# SparkFun_Si4707_Breakout.net
KiCad netlist of a schematic drawn in EAGLE
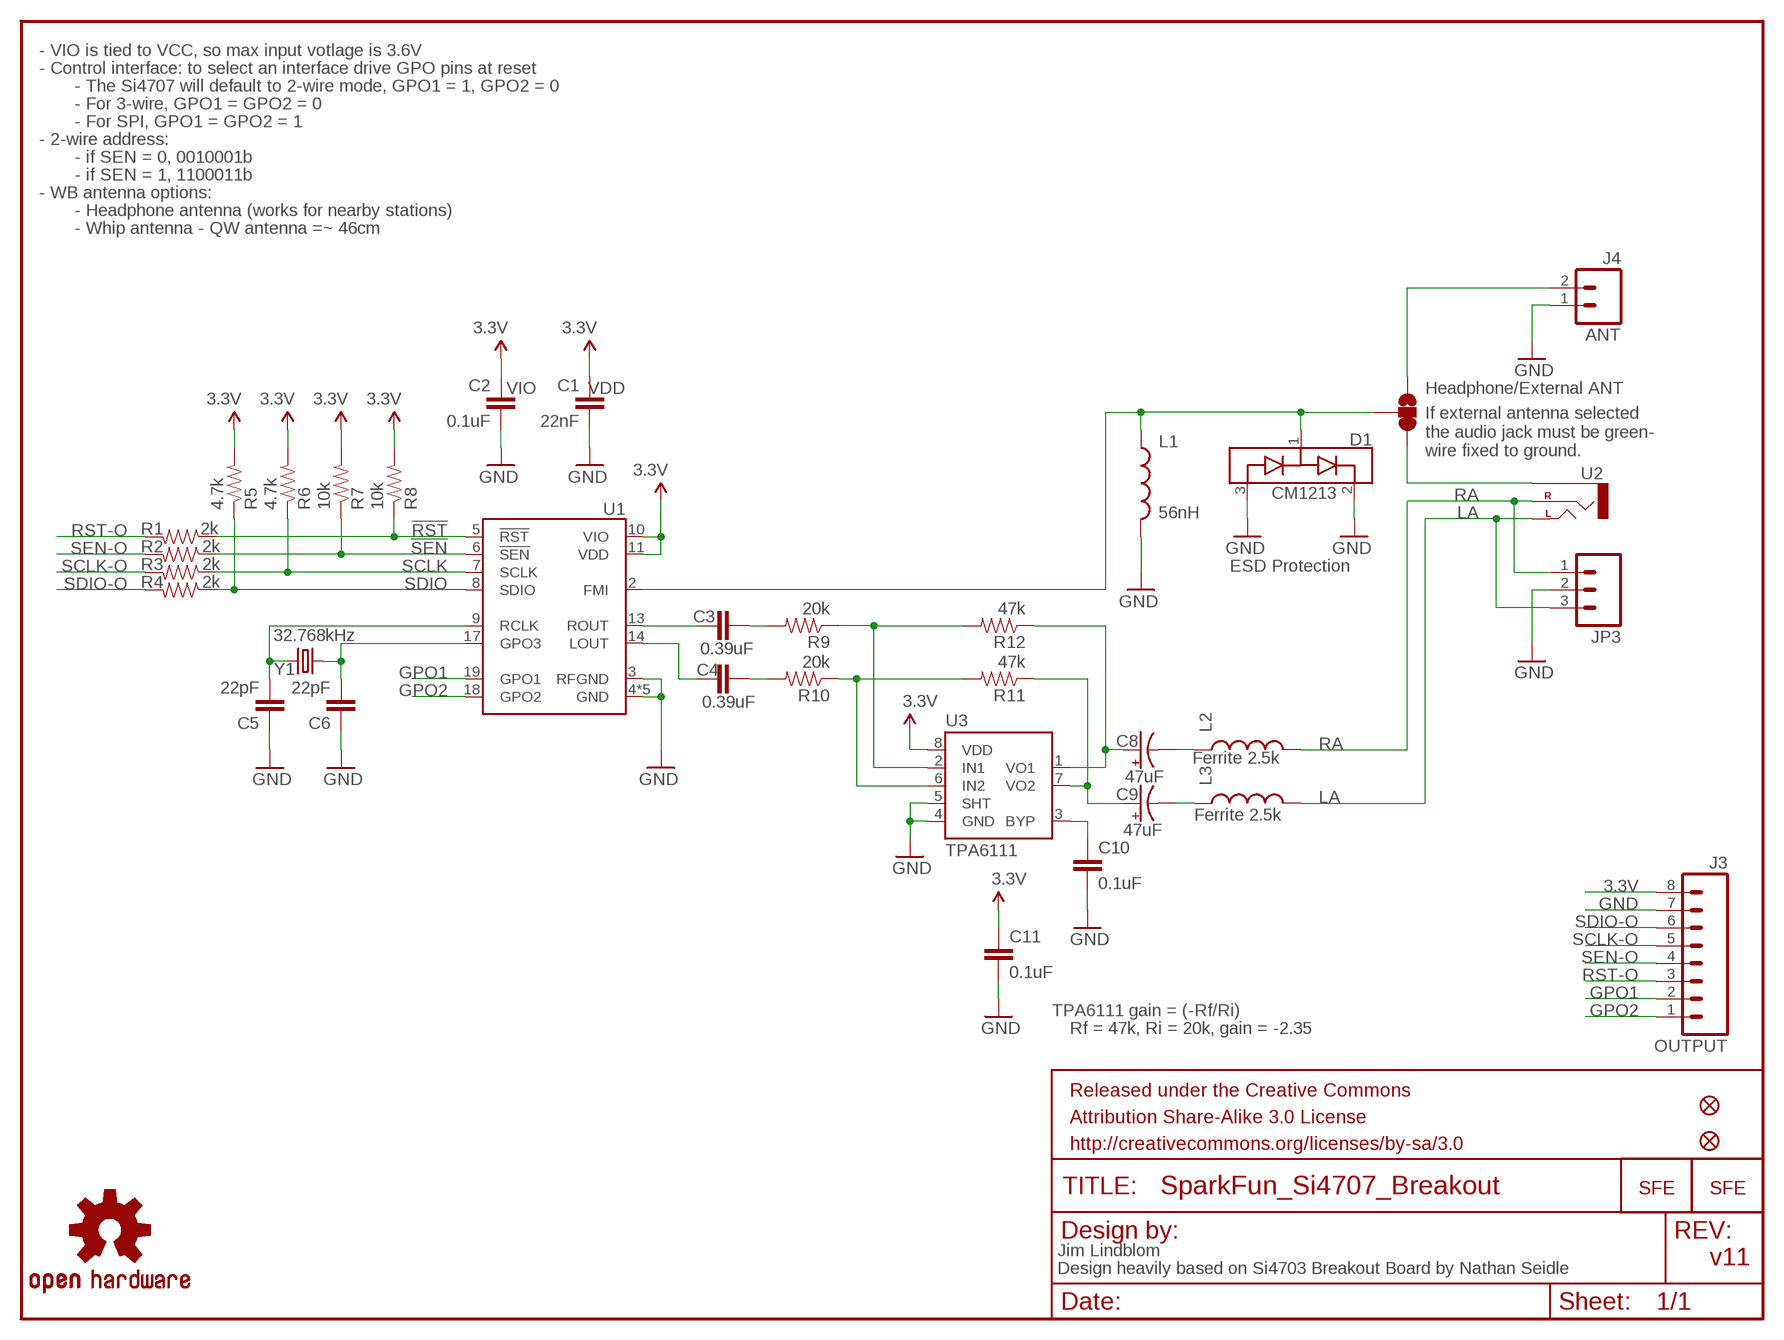
[diagram p0: schematic, sheet 1]

(export (version "E")
  (design (tool "Eeschema 10.0.6"))
  (components
    (comp (ref "C1")
      (value "22nF")
      (footprint "eagle-import:0402-CAP")
      (libsource (lib "eagle-import") (part "CAP0402-CAP"))
    )
    (comp (ref "C2")
      (value "0.1uF")
      (footprint "eagle-import:0402-CAP")
      (libsource (lib "eagle-import") (part "CAP0402-CAP"))
    )
    (comp (ref "C3")
      (value "0.39uF")
      (footprint "eagle-import:0402-CAP")
      (libsource (lib "eagle-import") (part "CAP0402-CAP"))
    )
    (comp (ref "C4")
      (value "0.39uF")
      (footprint "eagle-import:0402-CAP")
      (libsource (lib "eagle-import") (part "CAP0402-CAP"))
    )
    (comp (ref "C5")
      (value "22pF")
      (footprint "eagle-import:0402-CAP")
      (libsource (lib "eagle-import") (part "CAP0402-CAP"))
    )
    (comp (ref "C6")
      (value "22pF")
      (footprint "eagle-import:0402-CAP")
      (libsource (lib "eagle-import") (part "CAP0402-CAP"))
    )
    (comp (ref "C8")
      (value "47uF")
      (footprint "eagle-import:EIA3528")
      (libsource (lib "eagle-import") (part "CAP_POL3528"))
    )
    (comp (ref "C9")
      (value "47uF")
      (footprint "eagle-import:EIA3528")
      (libsource (lib "eagle-import") (part "CAP_POL3528"))
    )
    (comp (ref "C10")
      (value "0.1uF")
      (footprint "eagle-import:0402-CAP")
      (libsource (lib "eagle-import") (part "CAP0402-CAP"))
    )
    (comp (ref "C11")
      (value "0.1uF")
      (footprint "eagle-import:0402-CAP")
      (libsource (lib "eagle-import") (part "CAP0402-CAP"))
    )
    (comp (ref "D1")
      (value "CM1213")
      (footprint "eagle-import:SOT23-3")
      (libsource (lib "eagle-import") (part "CM1213"))
    )
    (comp (ref "FRAME1")
      (value "FRAME-LETTER")
      (footprint "eagle-import:CREATIVE_COMMONS")
      (libsource (lib "eagle-import") (part "FRAME-LETTER"))
    )
    (comp (ref "J3")
      (value "OUTPUT")
      (footprint "eagle-import:1X08")
      (libsource (lib "eagle-import") (part "M081X08"))
    )
    (comp (ref "J4")
      (value "ANT")
      (footprint "eagle-import:1X02")
      (libsource (lib "eagle-import") (part "M02PTH"))
    )
    (comp (ref "JP1")
      (value "LOGO-SFENEW")
      (footprint "eagle-import:SFE-NEW-WEBLOGO")
      (libsource (lib "eagle-import") (part "LOGO-SFENEW"))
    )
    (comp (ref "JP2")
      (value "LOGO-SFESK")
      (footprint "eagle-import:SFE-LOGO-FLAME")
      (libsource (lib "eagle-import") (part "LOGO-SFESK"))
    )
    (comp (ref "JP3")
      (value "M03PTH")
      (footprint "eagle-import:1X03")
      (libsource (lib "eagle-import") (part "M03PTH"))
    )
    (comp (ref "JP4")
      (value "FIDUCIALUFIDUCIAL")
      (footprint "eagle-import:MICRO-FIDUCIAL")
      (libsource (lib "eagle-import") (part "FIDUCIALUFIDUCIAL"))
    )
    (comp (ref "JP5")
      (value "FIDUCIALUFIDUCIAL")
      (footprint "eagle-import:MICRO-FIDUCIAL")
      (libsource (lib "eagle-import") (part "FIDUCIALUFIDUCIAL"))
    )
    (comp (ref "L1")
      (value "56nH")
      (footprint "eagle-import:0603")
      (libsource (lib "eagle-import") (part "INDUCTOR0603"))
    )
    (comp (ref "L2")
      (value "Ferrite 2.5k")
      (footprint "eagle-import:C0402")
      (libsource (lib "eagle-import") (part "INDUCTOR0402"))
    )
    (comp (ref "L3")
      (value "Ferrite 2.5k")
      (footprint "eagle-import:C0402")
      (libsource (lib "eagle-import") (part "INDUCTOR0402"))
    )
    (comp (ref "R1")
      (value "2k")
      (footprint "eagle-import:0402-RES")
      (libsource (lib "eagle-import") (part "RESISTOR0402-RES"))
    )
    (comp (ref "R2")
      (value "2k")
      (footprint "eagle-import:0402-RES")
      (libsource (lib "eagle-import") (part "RESISTOR0402-RES"))
    )
    (comp (ref "R3")
      (value "2k")
      (footprint "eagle-import:0402-RES")
      (libsource (lib "eagle-import") (part "RESISTOR0402-RES"))
    )
    (comp (ref "R4")
      (value "2k")
      (footprint "eagle-import:0402-RES")
      (libsource (lib "eagle-import") (part "RESISTOR0402-RES"))
    )
    (comp (ref "R5")
      (value "4.7k")
      (footprint "eagle-import:0402-RES")
      (libsource (lib "eagle-import") (part "RESISTOR0402-RES"))
    )
    (comp (ref "R6")
      (value "4.7k")
      (footprint "eagle-import:0402-RES")
      (libsource (lib "eagle-import") (part "RESISTOR0402-RES"))
    )
    (comp (ref "R7")
      (value "10k")
      (footprint "eagle-import:0402-RES")
      (libsource (lib "eagle-import") (part "RESISTOR0402-RES"))
    )
    (comp (ref "R8")
      (value "10k")
      (footprint "eagle-import:0402-RES")
      (libsource (lib "eagle-import") (part "RESISTOR0402-RES"))
    )
    (comp (ref "R9")
      (value "20k")
      (footprint "eagle-import:0402-RES")
      (libsource (lib "eagle-import") (part "RESISTOR0402-RES"))
    )
    (comp (ref "R10")
      (value "20k")
      (footprint "eagle-import:0402-RES")
      (libsource (lib "eagle-import") (part "RESISTOR0402-RES"))
    )
    (comp (ref "R11")
      (value "47k")
      (footprint "eagle-import:0402-RES")
      (libsource (lib "eagle-import") (part "RESISTOR0402-RES"))
    )
    (comp (ref "R12")
      (value "47k")
      (footprint "eagle-import:0402-RES")
      (libsource (lib "eagle-import") (part "RESISTOR0402-RES"))
    )
    (comp (ref "SJ2")
      (value "SOLDERJUMPER_2WAYS")
      (footprint "eagle-import:SJ_3")
      (libsource (lib "eagle-import") (part "SOLDERJUMPER_2WAYS"))
    )
    (comp (ref "U$2")
      (value "OSHW-LOGOS")
      (footprint "eagle-import:OSHW-LOGO-S")
      (libsource (lib "eagle-import") (part "OSHW-LOGOS"))
    )
    (comp (ref "U1")
      (value "SI4707")
      (footprint "eagle-import:SI470X")
      (libsource (lib "eagle-import") (part "SI4707"))
    )
    (comp (ref "U2")
      (value "AUDIO-JACKSMD2")
      (footprint "eagle-import:AUDIO-JACK-3.5MM-SMD")
      (libsource (lib "eagle-import") (part "AUDIO-JACKSMD2"))
    )
    (comp (ref "U3")
      (value "TPA6111")
      (footprint "eagle-import:SPARKFUN_SO08")
      (libsource (lib "eagle-import") (part "SPARKFUN_TPA6111SMD"))
    )
    (comp (ref "Y1")
      (value "32.768kHz")
      (footprint "eagle-import:CRYSTAL-32KHZ-SMD")
      (libsource (lib "eagle-import") (part "CRYSTAL32-SMD"))
    )
  )
  (nets
    (net (code "1") (name "/GPO1") (class "Default")
      (node (ref "J3") (pin "2") (pinfunction "2_2") (pintype "passive"))
      (node (ref "U1") (pin "19") (pinfunction "GPO1_19") (pintype "bidirectional"))
    )
    (net (code "2") (name "/GPO2") (class "Default")
      (node (ref "J3") (pin "1") (pinfunction "1_1") (pintype "passive"))
      (node (ref "U1") (pin "18") (pinfunction "GPO2_18") (pintype "bidirectional"))
    )
    (net (code "3") (name "/LA") (class "Default")
      (node (ref "JP3") (pin "3") (pinfunction "3_3") (pintype "passive"))
      (node (ref "L3") (pin "2") (pinfunction "2_2") (pintype "passive"))
      (node (ref "U2") (pin "TIP") (pinfunction "LEFT_TIP") (pintype "bidirectional"))
    )
    (net (code "4") (name "/RA") (class "Default")
      (node (ref "JP3") (pin "1") (pinfunction "1_1") (pintype "passive"))
      (node (ref "L2") (pin "2") (pinfunction "2_2") (pintype "passive"))
      (node (ref "U2") (pin "RING") (pinfunction "RIGHT_RING") (pintype "bidirectional"))
    )
    (net (code "5") (name "/RST-O") (class "Default")
      (node (ref "J3") (pin "3") (pinfunction "3_3") (pintype "passive"))
      (node (ref "R1") (pin "2") (pinfunction "2_2") (pintype "passive"))
    )
    (net (code "6") (name "/SCLK") (class "Default")
      (node (ref "R3") (pin "1") (pinfunction "1_1") (pintype "passive"))
      (node (ref "R6") (pin "1") (pinfunction "1_1") (pintype "passive"))
      (node (ref "U1") (pin "7") (pinfunction "SCLK_7") (pintype "bidirectional"))
    )
    (net (code "7") (name "/SCLK-O") (class "Default")
      (node (ref "J3") (pin "5") (pinfunction "5_5") (pintype "passive"))
      (node (ref "R3") (pin "2") (pinfunction "2_2") (pintype "passive"))
    )
    (net (code "8") (name "/SDIO") (class "Default")
      (node (ref "R4") (pin "1") (pinfunction "1_1") (pintype "passive"))
      (node (ref "R5") (pin "1") (pinfunction "1_1") (pintype "passive"))
      (node (ref "U1") (pin "8") (pinfunction "SDIO_8") (pintype "bidirectional"))
    )
    (net (code "9") (name "/SDIO-O") (class "Default")
      (node (ref "J3") (pin "6") (pinfunction "6_6") (pintype "passive"))
      (node (ref "R4") (pin "2") (pinfunction "2_2") (pintype "passive"))
    )
    (net (code "10") (name "/SEN-O") (class "Default")
      (node (ref "J3") (pin "4") (pinfunction "4_4") (pintype "passive"))
      (node (ref "R2") (pin "2") (pinfunction "2_2") (pintype "passive"))
    )
    (net (code "11") (name "/~{RST}") (class "Default")
      (node (ref "R1") (pin "1") (pinfunction "1_1") (pintype "passive"))
      (node (ref "R8") (pin "1") (pinfunction "1_1") (pintype "passive"))
      (node (ref "U1") (pin "5") (pinfunction "~{RST}_5") (pintype "bidirectional"))
    )
    (net (code "12") (name "/~{SEN}") (class "Default")
      (node (ref "R2") (pin "1") (pinfunction "1_1") (pintype "passive"))
      (node (ref "R7") (pin "1") (pinfunction "1_1") (pintype "passive"))
      (node (ref "U1") (pin "6") (pinfunction "~{SEN}_6") (pintype "bidirectional"))
    )
    (net (code "13") (name "3.3V") (class "Default")
      (node (ref "C1") (pin "1") (pinfunction "1_1") (pintype "passive"))
      (node (ref "C11") (pin "1") (pinfunction "1_1") (pintype "passive"))
      (node (ref "C2") (pin "1") (pinfunction "1_1") (pintype "passive"))
      (node (ref "J3") (pin "8") (pinfunction "8_8") (pintype "passive"))
      (node (ref "R5") (pin "2") (pinfunction "2_2") (pintype "passive"))
      (node (ref "R6") (pin "2") (pinfunction "2_2") (pintype "passive"))
      (node (ref "R7") (pin "2") (pinfunction "2_2") (pintype "passive"))
      (node (ref "R8") (pin "2") (pinfunction "2_2") (pintype "passive"))
      (node (ref "U1") (pin "10") (pinfunction "VIO_10") (pintype "bidirectional"))
      (node (ref "U1") (pin "11") (pinfunction "VDD_11") (pintype "bidirectional"))
      (node (ref "U3") (pin "8") (pinfunction "VDD_8") (pintype "bidirectional"))
    )
    (net (code "14") (name "GND") (class "Default")
      (node (ref "C1") (pin "2") (pinfunction "2_2") (pintype "passive"))
      (node (ref "C10") (pin "2") (pinfunction "2_2") (pintype "passive"))
      (node (ref "C11") (pin "2") (pinfunction "2_2") (pintype "passive"))
      (node (ref "C2") (pin "2") (pinfunction "2_2") (pintype "passive"))
      (node (ref "C5") (pin "1") (pinfunction "1_1") (pintype "passive"))
      (node (ref "C6") (pin "1") (pinfunction "1_1") (pintype "passive"))
      (node (ref "D1") (pin "2") (pinfunction "VP_2") (pintype "bidirectional"))
      (node (ref "D1") (pin "3") (pinfunction "VN_3") (pintype "bidirectional"))
      (node (ref "J3") (pin "7") (pinfunction "7_7") (pintype "passive"))
      (node (ref "J4") (pin "1") (pinfunction "1_1") (pintype "passive"))
      (node (ref "JP3") (pin "2") (pinfunction "2_2") (pintype "passive"))
      (node (ref "L1") (pin "2") (pinfunction "2_2") (pintype "passive"))
      (node (ref "U1") (pin "12") (pinfunction "GND_12") (pintype "bidirectional"))
      (node (ref "U1") (pin "15") (pinfunction "GND_15") (pintype "bidirectional"))
      (node (ref "U1") (pin "16") (pinfunction "GND_16") (pintype "bidirectional"))
      (node (ref "U1") (pin "21") (pinfunction "GND_21") (pintype "bidirectional"))
      (node (ref "U1") (pin "3") (pinfunction "RFGND_3") (pintype "bidirectional"))
      (node (ref "U1") (pin "4") (pinfunction "GND_4") (pintype "bidirectional"))
      (node (ref "U3") (pin "4") (pinfunction "GND_4") (pintype "bidirectional"))
      (node (ref "U3") (pin "5") (pinfunction "SHT_5") (pintype "bidirectional"))
    )
    (net (code "15") (name "Net-(C3-Pad2)") (class "Default")
      (node (ref "C3") (pin "2") (pinfunction "2_2") (pintype "passive"))
      (node (ref "R9") (pin "2") (pinfunction "2_2") (pintype "passive"))
    )
    (net (code "16") (name "Net-(C4-Pad2)") (class "Default")
      (node (ref "C4") (pin "2") (pinfunction "2_2") (pintype "passive"))
      (node (ref "R10") (pin "2") (pinfunction "2_2") (pintype "passive"))
    )
    (net (code "17") (name "Net-(C8-+)") (class "Default")
      (node (ref "C8") (pin "A") (pinfunction "+_A") (pintype "passive"))
      (node (ref "R12") (pin "1") (pinfunction "1_1") (pintype "passive"))
      (node (ref "U3") (pin "1") (pinfunction "VO1_1") (pintype "bidirectional"))
    )
    (net (code "18") (name "Net-(C8--)") (class "Default")
      (node (ref "C8") (pin "C") (pinfunction "-_C") (pintype "passive"))
      (node (ref "L2") (pin "1") (pinfunction "1_1") (pintype "passive"))
    )
    (net (code "19") (name "Net-(C9-+)") (class "Default")
      (node (ref "C9") (pin "A") (pinfunction "+_A") (pintype "passive"))
      (node (ref "R11") (pin "1") (pinfunction "1_1") (pintype "passive"))
      (node (ref "U3") (pin "7") (pinfunction "VO2_7") (pintype "bidirectional"))
    )
    (net (code "20") (name "Net-(C9--)") (class "Default")
      (node (ref "C9") (pin "C") (pinfunction "-_C") (pintype "passive"))
      (node (ref "L3") (pin "1") (pinfunction "1_1") (pintype "passive"))
    )
    (net (code "21") (name "Net-(D1-CH1)") (class "Default")
      (node (ref "D1") (pin "1") (pinfunction "CH1_1") (pintype "bidirectional"))
      (node (ref "L1") (pin "1") (pinfunction "1_1") (pintype "passive"))
      (node (ref "SJ2") (pin "2") (pinfunction "2_2") (pintype "passive"))
      (node (ref "U1") (pin "2") (pinfunction "FMI_2") (pintype "bidirectional"))
    )
    (net (code "22") (name "Net-(J4-Pad2)") (class "Default")
      (node (ref "J4") (pin "2") (pinfunction "2_2") (pintype "passive"))
      (node (ref "SJ2") (pin "3") (pinfunction "3_3") (pintype "passive"))
    )
    (net (code "23") (name "Net-(SJ2-Pad1)") (class "Default")
      (node (ref "SJ2") (pin "1") (pinfunction "1_1") (pintype "passive"))
      (node (ref "U2") (pin "SLEEVE") (pinfunction "SLEEVE_SLEEVE") (pintype "bidirectional"))
    )
    (net (code "24") (name "Net-(U1-GPO3)") (class "Default")
      (node (ref "C6") (pin "2") (pinfunction "2_2") (pintype "passive"))
      (node (ref "U1") (pin "17") (pinfunction "GPO3_17") (pintype "bidirectional"))
      (node (ref "Y1") (pin "X1") (pinfunction "1_X1") (pintype "passive"))
    )
    (net (code "25") (name "Net-(U1-LOUT)") (class "Default")
      (node (ref "C4") (pin "1") (pinfunction "1_1") (pintype "passive"))
      (node (ref "U1") (pin "14") (pinfunction "LOUT_14") (pintype "bidirectional"))
    )
    (net (code "26") (name "Net-(U1-RCLK)") (class "Default")
      (node (ref "C5") (pin "2") (pinfunction "2_2") (pintype "passive"))
      (node (ref "U1") (pin "9") (pinfunction "RCLK_9") (pintype "bidirectional"))
      (node (ref "Y1") (pin "X2") (pinfunction "2_X2") (pintype "passive"))
    )
    (net (code "27") (name "Net-(U1-ROUT)") (class "Default")
      (node (ref "C3") (pin "1") (pinfunction "1_1") (pintype "passive"))
      (node (ref "U1") (pin "13") (pinfunction "ROUT_13") (pintype "bidirectional"))
    )
    (net (code "28") (name "Net-(U3-BYP)") (class "Default")
      (node (ref "C10") (pin "1") (pinfunction "1_1") (pintype "passive"))
      (node (ref "U3") (pin "3") (pinfunction "BYP_3") (pintype "bidirectional"))
    )
    (net (code "29") (name "Net-(U3-IN1)") (class "Default")
      (node (ref "R12") (pin "2") (pinfunction "2_2") (pintype "passive"))
      (node (ref "R9") (pin "1") (pinfunction "1_1") (pintype "passive"))
      (node (ref "U3") (pin "2") (pinfunction "IN1_2") (pintype "bidirectional"))
    )
    (net (code "30") (name "Net-(U3-IN2)") (class "Default")
      (node (ref "R10") (pin "1") (pinfunction "1_1") (pintype "passive"))
      (node (ref "R11") (pin "2") (pinfunction "2_2") (pintype "passive"))
      (node (ref "U3") (pin "6") (pinfunction "IN2_6") (pintype "bidirectional"))
    )
  )
)
